# design.net
KiCad netlist of a schematic drawn in Altium Designer
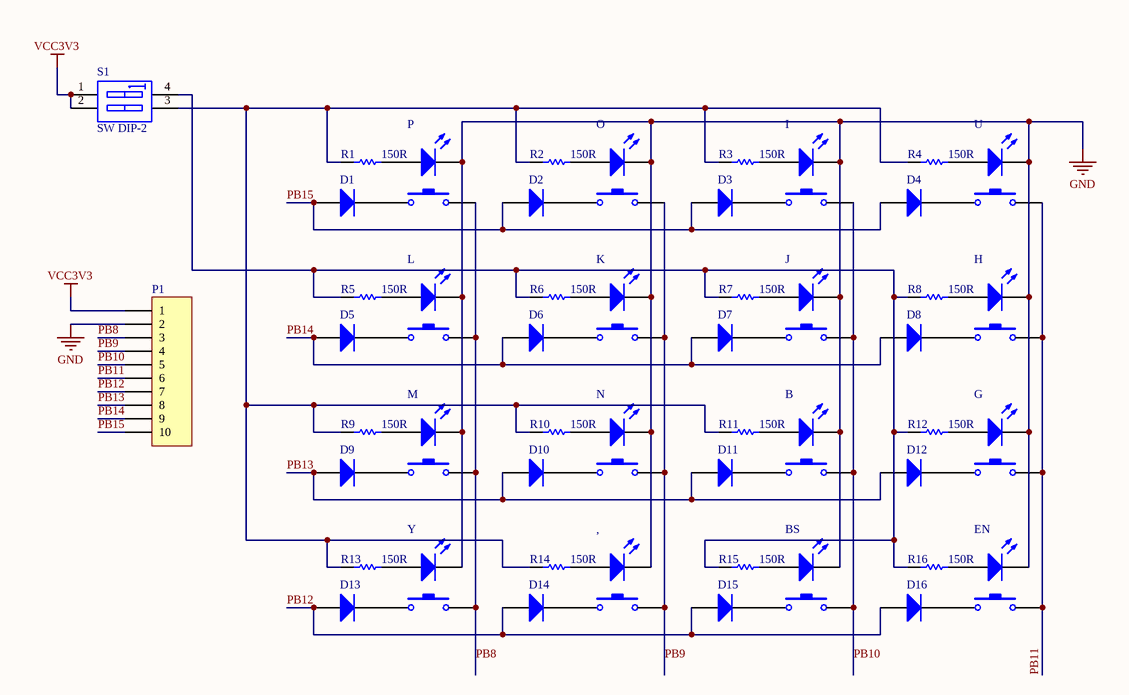
[diagram p0: 键盘.SchDoc]

(export (version "E")
  (design (tool "Eeschema 10.0.6"))
  (components
    (comp (ref ",") (value "MX5") (footprint "MX5F") (libsource (lib "lyq") (part "MX5")))
    (comp (ref "B") (value "MX5") (footprint "MX5F") (libsource (lib "lyq") (part "MX5")))
    (comp (ref "BS") (value "MX5") (footprint "MX5F") (libsource (lib "lyq") (part "MX5")))
    (comp (ref "D1")
      (value "Diode")
      (footprint "贴片二极管")
      (description "Default Diode")
      (fields (field (name "PUBLISHER") "Altium Limited"))
      (libsource (lib "lyq") (part "Diode"))
    )
    (comp (ref "D2")
      (value "Diode")
      (footprint "贴片二极管")
      (description "Default Diode")
      (fields (field (name "PUBLISHER") "Altium Limited"))
      (libsource (lib "lyq") (part "Diode"))
    )
    (comp (ref "D3")
      (value "Diode")
      (footprint "贴片二极管")
      (description "Default Diode")
      (fields (field (name "PUBLISHER") "Altium Limited"))
      (libsource (lib "lyq") (part "Diode"))
    )
    (comp (ref "D4")
      (value "Diode")
      (footprint "贴片二极管")
      (description "Default Diode")
      (fields (field (name "PUBLISHER") "Altium Limited"))
      (libsource (lib "lyq") (part "Diode"))
    )
    (comp (ref "D5")
      (value "Diode")
      (footprint "贴片二极管")
      (description "Default Diode")
      (fields (field (name "PUBLISHER") "Altium Limited"))
      (libsource (lib "lyq") (part "Diode"))
    )
    (comp (ref "D6")
      (value "Diode")
      (footprint "贴片二极管")
      (description "Default Diode")
      (fields (field (name "PUBLISHER") "Altium Limited"))
      (libsource (lib "lyq") (part "Diode"))
    )
    (comp (ref "D7")
      (value "Diode")
      (footprint "贴片二极管")
      (description "Default Diode")
      (fields (field (name "PUBLISHER") "Altium Limited"))
      (libsource (lib "lyq") (part "Diode"))
    )
    (comp (ref "D8")
      (value "Diode")
      (footprint "贴片二极管")
      (description "Default Diode")
      (fields (field (name "PUBLISHER") "Altium Limited"))
      (libsource (lib "lyq") (part "Diode"))
    )
    (comp (ref "D9")
      (value "Diode")
      (footprint "贴片二极管")
      (description "Default Diode")
      (fields (field (name "PUBLISHER") "Altium Limited"))
      (libsource (lib "lyq") (part "Diode"))
    )
    (comp (ref "D10")
      (value "Diode")
      (footprint "贴片二极管")
      (description "Default Diode")
      (fields (field (name "PUBLISHER") "Altium Limited"))
      (libsource (lib "lyq") (part "Diode"))
    )
    (comp (ref "D11")
      (value "Diode")
      (footprint "贴片二极管")
      (description "Default Diode")
      (fields (field (name "PUBLISHER") "Altium Limited"))
      (libsource (lib "lyq") (part "Diode"))
    )
    (comp (ref "D12")
      (value "Diode")
      (footprint "贴片二极管")
      (description "Default Diode")
      (fields (field (name "PUBLISHER") "Altium Limited"))
      (libsource (lib "lyq") (part "Diode"))
    )
    (comp (ref "D13")
      (value "Diode")
      (footprint "贴片二极管")
      (description "Default Diode")
      (fields (field (name "PUBLISHER") "Altium Limited"))
      (libsource (lib "lyq") (part "Diode"))
    )
    (comp (ref "D14")
      (value "Diode")
      (footprint "贴片二极管")
      (description "Default Diode")
      (fields (field (name "PUBLISHER") "Altium Limited"))
      (libsource (lib "lyq") (part "Diode"))
    )
    (comp (ref "D15")
      (value "Diode")
      (footprint "贴片二极管")
      (description "Default Diode")
      (fields (field (name "PUBLISHER") "Altium Limited"))
      (libsource (lib "lyq") (part "Diode"))
    )
    (comp (ref "D16")
      (value "Diode")
      (footprint "贴片二极管")
      (description "Default Diode")
      (fields (field (name "PUBLISHER") "Altium Limited"))
      (libsource (lib "lyq") (part "Diode"))
    )
    (comp (ref "EN") (value "MX5") (footprint "MX5F - 2") (libsource (lib "lyq") (part "MX5")))
    (comp (ref "G") (value "MX5") (footprint "MX5F") (libsource (lib "lyq") (part "MX5")))
    (comp (ref "H") (value "MX5") (footprint "MX5F") (libsource (lib "lyq") (part "MX5")))
    (comp (ref "I") (value "MX5") (footprint "MX5F") (libsource (lib "lyq") (part "MX5")))
    (comp (ref "J") (value "MX5") (footprint "MX5F") (libsource (lib "lyq") (part "MX5")))
    (comp (ref "K") (value "MX5") (footprint "MX5F") (libsource (lib "lyq") (part "MX5")))
    (comp (ref "L") (value "MX5") (footprint "MX5F") (libsource (lib "lyq") (part "MX5")))
    (comp (ref "M") (value "MX5") (footprint "MX5F") (libsource (lib "lyq") (part "MX5")))
    (comp (ref "N") (value "MX5") (footprint "MX5F") (libsource (lib "lyq") (part "MX5")))
    (comp (ref "O") (value "MX5") (footprint "MX5F") (libsource (lib "lyq") (part "MX5")))
    (comp (ref "P") (value "MX5") (footprint "MX5F") (libsource (lib "lyq") (part "MX5")))
    (comp (ref "P1")
      (value "PIN10")
      (footprint "PIN10")
      (description "Header, 10-Pin")
      (fields (field (name "PUBLISHER") "Altium Limited"))
      (libsource (lib "lyq") (part "PIN10"))
    )
    (comp (ref "R1")
      (value "150R")
      (footprint "0805")
      (description "Resistor")
      (fields (field (name "Comment") "Res") (field (name "PUBLISHER") "Altium Limited"))
      (libsource (lib "lyq") (part "Res"))
    )
    (comp (ref "R2")
      (value "150R")
      (footprint "0805")
      (description "Resistor")
      (fields (field (name "Comment") "Res") (field (name "PUBLISHER") "Altium Limited"))
      (libsource (lib "lyq") (part "Res"))
    )
    (comp (ref "R3")
      (value "150R")
      (footprint "0805")
      (description "Resistor")
      (fields (field (name "Comment") "Res") (field (name "PUBLISHER") "Altium Limited"))
      (libsource (lib "lyq") (part "Res"))
    )
    (comp (ref "R4")
      (value "150R")
      (footprint "0805")
      (description "Resistor")
      (fields (field (name "Comment") "Res") (field (name "PUBLISHER") "Altium Limited"))
      (libsource (lib "lyq") (part "Res"))
    )
    (comp (ref "R5")
      (value "150R")
      (footprint "0805")
      (description "Resistor")
      (fields (field (name "Comment") "Res") (field (name "PUBLISHER") "Altium Limited"))
      (libsource (lib "lyq") (part "Res"))
    )
    (comp (ref "R6")
      (value "150R")
      (footprint "0805")
      (description "Resistor")
      (fields (field (name "Comment") "Res") (field (name "PUBLISHER") "Altium Limited"))
      (libsource (lib "lyq") (part "Res"))
    )
    (comp (ref "R7")
      (value "150R")
      (footprint "0805")
      (description "Resistor")
      (fields (field (name "Comment") "Res") (field (name "PUBLISHER") "Altium Limited"))
      (libsource (lib "lyq") (part "Res"))
    )
    (comp (ref "R8")
      (value "150R")
      (footprint "0805")
      (description "Resistor")
      (fields (field (name "Comment") "Res") (field (name "PUBLISHER") "Altium Limited"))
      (libsource (lib "lyq") (part "Res"))
    )
    (comp (ref "R9")
      (value "150R")
      (footprint "0805")
      (description "Resistor")
      (fields (field (name "Comment") "Res") (field (name "PUBLISHER") "Altium Limited"))
      (libsource (lib "lyq") (part "Res"))
    )
    (comp (ref "R10")
      (value "150R")
      (footprint "0805")
      (description "Resistor")
      (fields (field (name "Comment") "Res") (field (name "PUBLISHER") "Altium Limited"))
      (libsource (lib "lyq") (part "Res"))
    )
    (comp (ref "R11")
      (value "150R")
      (footprint "0805")
      (description "Resistor")
      (fields (field (name "Comment") "Res") (field (name "PUBLISHER") "Altium Limited"))
      (libsource (lib "lyq") (part "Res"))
    )
    (comp (ref "R12")
      (value "150R")
      (footprint "0805")
      (description "Resistor")
      (fields (field (name "Comment") "Res") (field (name "PUBLISHER") "Altium Limited"))
      (libsource (lib "lyq") (part "Res"))
    )
    (comp (ref "R13")
      (value "150R")
      (footprint "0805")
      (description "Resistor")
      (fields (field (name "Comment") "Res") (field (name "PUBLISHER") "Altium Limited"))
      (libsource (lib "lyq") (part "Res"))
    )
    (comp (ref "R14")
      (value "150R")
      (footprint "0805")
      (description "Resistor")
      (fields (field (name "Comment") "Res") (field (name "PUBLISHER") "Altium Limited"))
      (libsource (lib "lyq") (part "Res"))
    )
    (comp (ref "R15")
      (value "150R")
      (footprint "0805")
      (description "Resistor")
      (fields (field (name "Comment") "Res") (field (name "PUBLISHER") "Altium Limited"))
      (libsource (lib "lyq") (part "Res"))
    )
    (comp (ref "R16")
      (value "150R")
      (footprint "0805")
      (description "Resistor")
      (fields (field (name "Comment") "Res") (field (name "PUBLISHER") "Altium Limited"))
      (libsource (lib "lyq") (part "Res"))
    )
    (comp (ref "S1")
      (value "SW DIP-2")
      (footprint "SW-DIP-2")
      (description "DIP Switch, 2 Position, SPST")
      (fields (field (name "PUBLISHER") "Altium Limited"))
      (libsource (lib "lyq") (part "SW DIP-2"))
    )
    (comp (ref "U") (value "MX5") (footprint "MX5F") (libsource (lib "lyq") (part "MX5")))
    (comp (ref "Y") (value "MX5") (footprint "MX5F") (libsource (lib "lyq") (part "MX5")))
  )
  (nets
    (net (code "1") (name "/PB8") (class "Default")
      (node (ref "L") (pin "2") (pinfunction "2_2") (pintype "passive"))
      (node (ref "M") (pin "2") (pinfunction "2_2") (pintype "passive"))
      (node (ref "P") (pin "2") (pinfunction "2_2") (pintype "passive"))
      (node (ref "P1") (pin "3") (pinfunction "3_3") (pintype "passive"))
      (node (ref "Y") (pin "2") (pinfunction "2_2") (pintype "passive"))
    )
    (net (code "2") (name "/PB9") (class "Default")
      (node (ref ",") (pin "2") (pinfunction "2_2") (pintype "passive"))
      (node (ref "K") (pin "2") (pinfunction "2_2") (pintype "passive"))
      (node (ref "N") (pin "2") (pinfunction "2_2") (pintype "passive"))
      (node (ref "O") (pin "2") (pinfunction "2_2") (pintype "passive"))
      (node (ref "P1") (pin "4") (pinfunction "4_4") (pintype "passive"))
    )
    (net (code "3") (name "/PB10") (class "Default")
      (node (ref "B") (pin "2") (pinfunction "2_2") (pintype "passive"))
      (node (ref "BS") (pin "2") (pinfunction "2_2") (pintype "passive"))
      (node (ref "I") (pin "2") (pinfunction "2_2") (pintype "passive"))
      (node (ref "J") (pin "2") (pinfunction "2_2") (pintype "passive"))
      (node (ref "P1") (pin "5") (pinfunction "5_5") (pintype "passive"))
    )
    (net (code "4") (name "/PB11") (class "Default")
      (node (ref "EN") (pin "2") (pinfunction "2_2") (pintype "passive"))
      (node (ref "G") (pin "2") (pinfunction "2_2") (pintype "passive"))
      (node (ref "H") (pin "2") (pinfunction "2_2") (pintype "passive"))
      (node (ref "P1") (pin "6") (pinfunction "6_6") (pintype "passive"))
      (node (ref "U") (pin "2") (pinfunction "2_2") (pintype "passive"))
    )
    (net (code "5") (name "/PB12") (class "Default")
      (node (ref "D13") (pin "1") (pinfunction "A_1") (pintype "passive"))
      (node (ref "D14") (pin "1") (pinfunction "A_1") (pintype "passive"))
      (node (ref "D15") (pin "1") (pinfunction "A_1") (pintype "passive"))
      (node (ref "D16") (pin "1") (pinfunction "A_1") (pintype "passive"))
      (node (ref "P1") (pin "7") (pinfunction "7_7") (pintype "passive"))
    )
    (net (code "6") (name "/PB13") (class "Default")
      (node (ref "D10") (pin "1") (pinfunction "A_1") (pintype "passive"))
      (node (ref "D11") (pin "1") (pinfunction "A_1") (pintype "passive"))
      (node (ref "D12") (pin "1") (pinfunction "A_1") (pintype "passive"))
      (node (ref "D9") (pin "1") (pinfunction "A_1") (pintype "passive"))
      (node (ref "P1") (pin "8") (pinfunction "8_8") (pintype "passive"))
    )
    (net (code "7") (name "/PB14") (class "Default")
      (node (ref "D5") (pin "1") (pinfunction "A_1") (pintype "passive"))
      (node (ref "D6") (pin "1") (pinfunction "A_1") (pintype "passive"))
      (node (ref "D7") (pin "1") (pinfunction "A_1") (pintype "passive"))
      (node (ref "D8") (pin "1") (pinfunction "A_1") (pintype "passive"))
      (node (ref "P1") (pin "9") (pinfunction "9_9") (pintype "passive"))
    )
    (net (code "8") (name "/PB15") (class "Default")
      (node (ref "D1") (pin "1") (pinfunction "A_1") (pintype "passive"))
      (node (ref "D2") (pin "1") (pinfunction "A_1") (pintype "passive"))
      (node (ref "D3") (pin "1") (pinfunction "A_1") (pintype "passive"))
      (node (ref "D4") (pin "1") (pinfunction "A_1") (pintype "passive"))
      (node (ref "P1") (pin "10") (pinfunction "10_10") (pintype "passive"))
    )
    (net (code "9") (name "GND") (class "Default")
      (node (ref ",") (pin "K") (pinfunction "K_K") (pintype "passive"))
      (node (ref "B") (pin "K") (pinfunction "K_K") (pintype "passive"))
      (node (ref "BS") (pin "K") (pinfunction "K_K") (pintype "passive"))
      (node (ref "EN") (pin "K") (pinfunction "K_K") (pintype "passive"))
      (node (ref "G") (pin "K") (pinfunction "K_K") (pintype "passive"))
      (node (ref "H") (pin "K") (pinfunction "K_K") (pintype "passive"))
      (node (ref "I") (pin "K") (pinfunction "K_K") (pintype "passive"))
      (node (ref "J") (pin "K") (pinfunction "K_K") (pintype "passive"))
      (node (ref "K") (pin "K") (pinfunction "K_K") (pintype "passive"))
      (node (ref "L") (pin "K") (pinfunction "K_K") (pintype "passive"))
      (node (ref "M") (pin "K") (pinfunction "K_K") (pintype "passive"))
      (node (ref "N") (pin "K") (pinfunction "K_K") (pintype "passive"))
      (node (ref "O") (pin "K") (pinfunction "K_K") (pintype "passive"))
      (node (ref "P") (pin "K") (pinfunction "K_K") (pintype "passive"))
      (node (ref "P1") (pin "2") (pinfunction "2_2") (pintype "passive"))
      (node (ref "U") (pin "K") (pinfunction "K_K") (pintype "passive"))
      (node (ref "Y") (pin "K") (pinfunction "K_K") (pintype "passive"))
    )
    (net (code "10") (name "Net-(,-PadA)") (class "Default")
      (node (ref ",") (pin "A") (pinfunction "A_A") (pintype "passive"))
      (node (ref "R14") (pin "2") (pinfunction "2_2") (pintype "passive"))
    )
    (net (code "11") (name "Net-(B-PadA)") (class "Default")
      (node (ref "B") (pin "A") (pinfunction "A_A") (pintype "passive"))
      (node (ref "R11") (pin "2") (pinfunction "2_2") (pintype "passive"))
    )
    (net (code "12") (name "Net-(BS-PadA)") (class "Default")
      (node (ref "BS") (pin "A") (pinfunction "A_A") (pintype "passive"))
      (node (ref "R15") (pin "2") (pinfunction "2_2") (pintype "passive"))
    )
    (net (code "13") (name "Net-(D1-K)") (class "Default")
      (node (ref "D1") (pin "2") (pinfunction "K_2") (pintype "passive"))
      (node (ref "P") (pin "1") (pinfunction "1_1") (pintype "passive"))
    )
    (net (code "14") (name "Net-(D2-K)") (class "Default")
      (node (ref "D2") (pin "2") (pinfunction "K_2") (pintype "passive"))
      (node (ref "O") (pin "1") (pinfunction "1_1") (pintype "passive"))
    )
    (net (code "15") (name "Net-(D3-K)") (class "Default")
      (node (ref "D3") (pin "2") (pinfunction "K_2") (pintype "passive"))
      (node (ref "I") (pin "1") (pinfunction "1_1") (pintype "passive"))
    )
    (net (code "16") (name "Net-(D4-K)") (class "Default")
      (node (ref "D4") (pin "2") (pinfunction "K_2") (pintype "passive"))
      (node (ref "U") (pin "1") (pinfunction "1_1") (pintype "passive"))
    )
    (net (code "17") (name "Net-(D5-K)") (class "Default")
      (node (ref "D5") (pin "2") (pinfunction "K_2") (pintype "passive"))
      (node (ref "L") (pin "1") (pinfunction "1_1") (pintype "passive"))
    )
    (net (code "18") (name "Net-(D6-K)") (class "Default")
      (node (ref "D6") (pin "2") (pinfunction "K_2") (pintype "passive"))
      (node (ref "K") (pin "1") (pinfunction "1_1") (pintype "passive"))
    )
    (net (code "19") (name "Net-(D7-K)") (class "Default")
      (node (ref "D7") (pin "2") (pinfunction "K_2") (pintype "passive"))
      (node (ref "J") (pin "1") (pinfunction "1_1") (pintype "passive"))
    )
    (net (code "20") (name "Net-(D8-K)") (class "Default")
      (node (ref "D8") (pin "2") (pinfunction "K_2") (pintype "passive"))
      (node (ref "H") (pin "1") (pinfunction "1_1") (pintype "passive"))
    )
    (net (code "21") (name "Net-(D9-K)") (class "Default")
      (node (ref "D9") (pin "2") (pinfunction "K_2") (pintype "passive"))
      (node (ref "M") (pin "1") (pinfunction "1_1") (pintype "passive"))
    )
    (net (code "22") (name "Net-(D10-K)") (class "Default")
      (node (ref "D10") (pin "2") (pinfunction "K_2") (pintype "passive"))
      (node (ref "N") (pin "1") (pinfunction "1_1") (pintype "passive"))
    )
    (net (code "23") (name "Net-(D11-K)") (class "Default")
      (node (ref "B") (pin "1") (pinfunction "1_1") (pintype "passive"))
      (node (ref "D11") (pin "2") (pinfunction "K_2") (pintype "passive"))
    )
    (net (code "24") (name "Net-(D12-K)") (class "Default")
      (node (ref "D12") (pin "2") (pinfunction "K_2") (pintype "passive"))
      (node (ref "G") (pin "1") (pinfunction "1_1") (pintype "passive"))
    )
    (net (code "25") (name "Net-(D13-K)") (class "Default")
      (node (ref "D13") (pin "2") (pinfunction "K_2") (pintype "passive"))
      (node (ref "Y") (pin "1") (pinfunction "1_1") (pintype "passive"))
    )
    (net (code "26") (name "Net-(D14-K)") (class "Default")
      (node (ref ",") (pin "1") (pinfunction "1_1") (pintype "passive"))
      (node (ref "D14") (pin "2") (pinfunction "K_2") (pintype "passive"))
    )
    (net (code "27") (name "Net-(D15-K)") (class "Default")
      (node (ref "BS") (pin "1") (pinfunction "1_1") (pintype "passive"))
      (node (ref "D15") (pin "2") (pinfunction "K_2") (pintype "passive"))
    )
    (net (code "28") (name "Net-(D16-K)") (class "Default")
      (node (ref "D16") (pin "2") (pinfunction "K_2") (pintype "passive"))
      (node (ref "EN") (pin "1") (pinfunction "1_1") (pintype "passive"))
    )
    (net (code "29") (name "Net-(EN-PadA)") (class "Default")
      (node (ref "EN") (pin "A") (pinfunction "A_A") (pintype "passive"))
      (node (ref "R16") (pin "2") (pinfunction "2_2") (pintype "passive"))
    )
    (net (code "30") (name "Net-(G-PadA)") (class "Default")
      (node (ref "G") (pin "A") (pinfunction "A_A") (pintype "passive"))
      (node (ref "R12") (pin "2") (pinfunction "2_2") (pintype "passive"))
    )
    (net (code "31") (name "Net-(H-PadA)") (class "Default")
      (node (ref "H") (pin "A") (pinfunction "A_A") (pintype "passive"))
      (node (ref "R8") (pin "2") (pinfunction "2_2") (pintype "passive"))
    )
    (net (code "32") (name "Net-(I-PadA)") (class "Default")
      (node (ref "I") (pin "A") (pinfunction "A_A") (pintype "passive"))
      (node (ref "R3") (pin "2") (pinfunction "2_2") (pintype "passive"))
    )
    (net (code "33") (name "Net-(J-PadA)") (class "Default")
      (node (ref "J") (pin "A") (pinfunction "A_A") (pintype "passive"))
      (node (ref "R7") (pin "2") (pinfunction "2_2") (pintype "passive"))
    )
    (net (code "34") (name "Net-(K-PadA)") (class "Default")
      (node (ref "K") (pin "A") (pinfunction "A_A") (pintype "passive"))
      (node (ref "R6") (pin "2") (pinfunction "2_2") (pintype "passive"))
    )
    (net (code "35") (name "Net-(L-PadA)") (class "Default")
      (node (ref "L") (pin "A") (pinfunction "A_A") (pintype "passive"))
      (node (ref "R5") (pin "2") (pinfunction "2_2") (pintype "passive"))
    )
    (net (code "36") (name "Net-(M-PadA)") (class "Default")
      (node (ref "M") (pin "A") (pinfunction "A_A") (pintype "passive"))
      (node (ref "R9") (pin "2") (pinfunction "2_2") (pintype "passive"))
    )
    (net (code "37") (name "Net-(N-PadA)") (class "Default")
      (node (ref "N") (pin "A") (pinfunction "A_A") (pintype "passive"))
      (node (ref "R10") (pin "2") (pinfunction "2_2") (pintype "passive"))
    )
    (net (code "38") (name "Net-(O-PadA)") (class "Default")
      (node (ref "O") (pin "A") (pinfunction "A_A") (pintype "passive"))
      (node (ref "R2") (pin "2") (pinfunction "2_2") (pintype "passive"))
    )
    (net (code "39") (name "Net-(P-PadA)") (class "Default")
      (node (ref "P") (pin "A") (pinfunction "A_A") (pintype "passive"))
      (node (ref "R1") (pin "2") (pinfunction "2_2") (pintype "passive"))
    )
    (net (code "40") (name "Net-(R4-Pad2)") (class "Default")
      (node (ref "R4") (pin "2") (pinfunction "2_2") (pintype "passive"))
      (node (ref "U") (pin "A") (pinfunction "A_A") (pintype "passive"))
    )
    (net (code "41") (name "Net-(R13-Pad2)") (class "Default")
      (node (ref "R13") (pin "2") (pinfunction "2_2") (pintype "passive"))
      (node (ref "Y") (pin "A") (pinfunction "A_A") (pintype "passive"))
    )
    (net (code "42") (name "Net-(S1-B1)") (class "Default")
      (node (ref "R12") (pin "1") (pinfunction "1_1") (pintype "passive"))
      (node (ref "R15") (pin "1") (pinfunction "1_1") (pintype "passive"))
      (node (ref "R16") (pin "1") (pinfunction "1_1") (pintype "passive"))
      (node (ref "R5") (pin "1") (pinfunction "1_1") (pintype "passive"))
      (node (ref "R6") (pin "1") (pinfunction "1_1") (pintype "passive"))
      (node (ref "R7") (pin "1") (pinfunction "1_1") (pintype "passive"))
      (node (ref "R8") (pin "1") (pinfunction "1_1") (pintype "passive"))
      (node (ref "S1") (pin "4") (pinfunction "B1_4") (pintype "passive"))
    )
    (net (code "43") (name "Net-(S1-B2)") (class "Default")
      (node (ref "R1") (pin "1") (pinfunction "1_1") (pintype "passive"))
      (node (ref "R10") (pin "1") (pinfunction "1_1") (pintype "passive"))
      (node (ref "R11") (pin "1") (pinfunction "1_1") (pintype "passive"))
      (node (ref "R13") (pin "1") (pinfunction "1_1") (pintype "passive"))
      (node (ref "R14") (pin "1") (pinfunction "1_1") (pintype "passive"))
      (node (ref "R2") (pin "1") (pinfunction "1_1") (pintype "passive"))
      (node (ref "R3") (pin "1") (pinfunction "1_1") (pintype "passive"))
      (node (ref "R4") (pin "1") (pinfunction "1_1") (pintype "passive"))
      (node (ref "R9") (pin "1") (pinfunction "1_1") (pintype "passive"))
      (node (ref "S1") (pin "3") (pinfunction "B2_3") (pintype "passive"))
    )
    (net (code "44") (name "VCC3V3") (class "Default")
      (node (ref "P1") (pin "1") (pinfunction "1_1") (pintype "passive"))
      (node (ref "S1") (pin "1") (pinfunction "A1_1") (pintype "passive"))
      (node (ref "S1") (pin "2") (pinfunction "A2_2") (pintype "passive"))
    )
  )
)
